# NIC_DP83848.net
KiCad netlist of a schematic drawn in Altium Designer
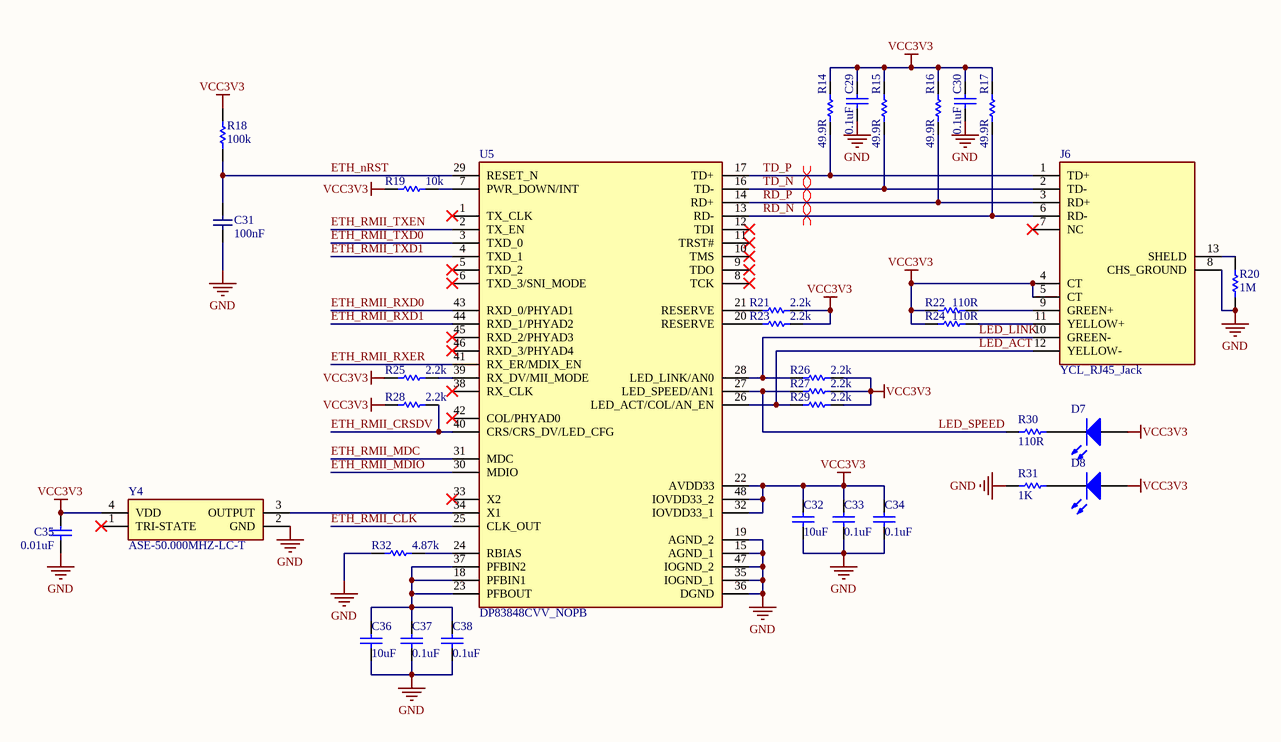
[diagram p0: NIC_DP83848.SchDoc]

(export (version "E")
  (design (tool "Eeschema 10.0.6"))
  (components
    (comp (ref "C29")
      (value "0.1uF")
      (footprint "SMD0603")
      (description "Capacitor (Semiconductor SIM Model)")
      (fields (field (name "PUBLISHER") "Altium Limited"))
      (libsource (lib "Miscellaneous Devices") (part "Cap Semi"))
    )
    (comp (ref "C30")
      (value "0.1uF")
      (footprint "SMD0603")
      (description "Capacitor (Semiconductor SIM Model)")
      (fields (field (name "PUBLISHER") "Altium Limited"))
      (libsource (lib "Miscellaneous Devices") (part "Cap Semi"))
    )
    (comp (ref "C31")
      (value "100nF")
      (footprint "SMD0603")
      (description "Capacitor (Semiconductor SIM Model)")
      (libsource (lib "SRV8") (part "Cap"))
    )
    (comp (ref "C32")
      (value "10uF")
      (footprint "SMD0603")
      (description "Capacitor (Semiconductor SIM Model)")
      (fields (field (name "PUBLISHER") "Altium Limited"))
      (libsource (lib "Miscellaneous Devices") (part "Cap Semi"))
    )
    (comp (ref "C33")
      (value "0.1uF")
      (footprint "SMD0603")
      (description "Capacitor (Semiconductor SIM Model)")
      (fields (field (name "PUBLISHER") "Altium Limited"))
      (libsource (lib "Miscellaneous Devices") (part "Cap Semi"))
    )
    (comp (ref "C34")
      (value "0.1uF")
      (footprint "SMD0603")
      (description "Capacitor (Semiconductor SIM Model)")
      (fields (field (name "PUBLISHER") "Altium Limited"))
      (libsource (lib "Miscellaneous Devices") (part "Cap Semi"))
    )
    (comp (ref "C35")
      (value "0.01uF")
      (footprint "SMD0603")
      (description "Capacitor (Semiconductor SIM Model)")
      (fields (field (name "Comment") "0.1uF") (field (name "PUBLISHER") "Altium Limited"))
      (libsource (lib "Miscellaneous Devices") (part "Cap Semi"))
    )
    (comp (ref "C36")
      (value "10uF")
      (footprint "SMD0603")
      (description "Capacitor (Semiconductor SIM Model)")
      (fields (field (name "PUBLISHER") "Altium Limited"))
      (libsource (lib "Miscellaneous Devices") (part "Cap Semi"))
    )
    (comp (ref "C37")
      (value "0.1uF")
      (footprint "SMD0603")
      (description "Capacitor (Semiconductor SIM Model)")
      (fields (field (name "PUBLISHER") "Altium Limited"))
      (libsource (lib "Miscellaneous Devices") (part "Cap Semi"))
    )
    (comp (ref "C38")
      (value "0.1uF")
      (footprint "SMD0603")
      (description "Capacitor (Semiconductor SIM Model)")
      (fields (field (name "PUBLISHER") "Altium Limited"))
      (libsource (lib "Miscellaneous Devices") (part "Cap Semi"))
    )
    (comp (ref "D7")
      (value "LED0")
      (footprint "SMD0603_LED")
      (description "Typical INFRARED GaAs LED")
      (fields (field (name "PUBLISHER") "Altium Limited"))
      (libsource (lib "Miscellaneous Devices") (part "LED0"))
    )
    (comp (ref "D8")
      (value "LED0")
      (footprint "SMD0603_LED")
      (description "Typical INFRARED GaAs LED")
      (fields (field (name "PUBLISHER") "Altium Limited"))
      (libsource (lib "Miscellaneous Devices") (part "LED0"))
    )
    (comp (ref "J6")
      (value "YCL_RJ45_Jack")
      (footprint "YCL_RJ45_Jack")
      (description "Connector")
      (fields (field (name "MANUFACTURER_PART_NUMBER") "J0011D21BNL"))
      (libsource (lib "ether_phy_lib") (part "YCL_RJ45_Jack"))
    )
    (comp (ref "R14")
      (value "49.9R")
      (footprint "SMD0603")
      (description "Semiconductor Resistor")
      (fields (field (name "PUBLISHER") "Altium Limited"))
      (libsource (lib "Miscellaneous Devices") (part "Res Semi"))
    )
    (comp (ref "R15")
      (value "49.9R")
      (footprint "SMD0603")
      (description "Semiconductor Resistor")
      (fields (field (name "PUBLISHER") "Altium Limited"))
      (libsource (lib "Miscellaneous Devices") (part "Res Semi"))
    )
    (comp (ref "R16")
      (value "49.9R")
      (footprint "SMD0603")
      (description "Semiconductor Resistor")
      (fields (field (name "PUBLISHER") "Altium Limited"))
      (libsource (lib "Miscellaneous Devices") (part "Res Semi"))
    )
    (comp (ref "R17")
      (value "49.9R")
      (footprint "SMD0603")
      (description "Semiconductor Resistor")
      (fields (field (name "PUBLISHER") "Altium Limited"))
      (libsource (lib "Miscellaneous Devices") (part "Res Semi"))
    )
    (comp (ref "R18")
      (value "100k")
      (footprint "SMD0603")
      (description "Semiconductor Resistor")
      (fields (field (name "Comment") "100K"))
      (libsource (lib "*") (part "Res"))
    )
    (comp (ref "R19")
      (value "10k")
      (footprint "SMD0603")
      (description "Semiconductor Resistor")
      (fields (field (name "PUBLISHER") "Altium Limited"))
      (libsource (lib "Miscellaneous Devices") (part "Res Semi"))
    )
    (comp (ref "R20")
      (value "1M")
      (footprint "SMD0603")
      (description "Semiconductor Resistor")
      (fields (field (name "PUBLISHER") "Altium Limited"))
      (libsource (lib "Miscellaneous Devices") (part "Res Semi"))
    )
    (comp (ref "R21")
      (value "2.2k")
      (footprint "SMD0603")
      (description "Semiconductor Resistor")
      (fields (field (name "PUBLISHER") "Altium Limited"))
      (libsource (lib "Miscellaneous Devices") (part "Res Semi"))
    )
    (comp (ref "R22")
      (value "110R")
      (footprint "SMD0603")
      (description "Semiconductor Resistor")
      (fields (field (name "PUBLISHER") "Altium Limited"))
      (libsource (lib "Miscellaneous Devices") (part "Res Semi"))
    )
    (comp (ref "R23")
      (value "2.2k")
      (footprint "SMD0603")
      (description "Semiconductor Resistor")
      (fields (field (name "PUBLISHER") "Altium Limited"))
      (libsource (lib "Miscellaneous Devices") (part "Res Semi"))
    )
    (comp (ref "R24")
      (value "110R")
      (footprint "SMD0603")
      (description "Semiconductor Resistor")
      (fields (field (name "PUBLISHER") "Altium Limited"))
      (libsource (lib "Miscellaneous Devices") (part "Res Semi"))
    )
    (comp (ref "R25")
      (value "2.2k")
      (footprint "SMD0603")
      (description "Semiconductor Resistor")
      (fields (field (name "PUBLISHER") "Altium Limited"))
      (libsource (lib "Miscellaneous Devices") (part "Res Semi"))
    )
    (comp (ref "R26")
      (value "2.2k")
      (footprint "SMD0603")
      (description "Semiconductor Resistor")
      (fields (field (name "PUBLISHER") "Altium Limited"))
      (libsource (lib "Miscellaneous Devices") (part "Res Semi"))
    )
    (comp (ref "R27")
      (value "2.2k")
      (footprint "SMD0603")
      (description "Semiconductor Resistor")
      (fields (field (name "PUBLISHER") "Altium Limited"))
      (libsource (lib "Miscellaneous Devices") (part "Res Semi"))
    )
    (comp (ref "R28")
      (value "2.2k")
      (footprint "SMD0603")
      (description "Semiconductor Resistor")
      (fields (field (name "PUBLISHER") "Altium Limited"))
      (libsource (lib "Miscellaneous Devices") (part "Res Semi"))
    )
    (comp (ref "R29")
      (value "2.2k")
      (footprint "SMD0603")
      (description "Semiconductor Resistor")
      (fields (field (name "PUBLISHER") "Altium Limited"))
      (libsource (lib "Miscellaneous Devices") (part "Res Semi"))
    )
    (comp (ref "R30")
      (value "110R")
      (footprint "SMD0603")
      (description "Semiconductor Resistor")
      (fields (field (name "Comment") "1K") (field (name "PUBLISHER") "Altium Limited"))
      (libsource (lib "Miscellaneous Devices") (part "Res Semi"))
    )
    (comp (ref "R31")
      (value "1K")
      (footprint "SMD0603")
      (description "Semiconductor Resistor")
      (fields (field (name "PUBLISHER") "Altium Limited"))
      (libsource (lib "Miscellaneous Devices") (part "Res Semi"))
    )
    (comp (ref "R32")
      (value "4.87k")
      (footprint "SMD0603")
      (description "Semiconductor Resistor")
      (fields (field (name "PUBLISHER") "Altium Limited"))
      (libsource (lib "Miscellaneous Devices") (part "Res Semi"))
    )
    (comp (ref "U5")
      (value "DP83848CVV_NOPB")
      (footprint "QFP50P900X900X160-48N")
      (description "Ethernet phy")
      (libsource (lib "ether_phy_lib") (part "DP83848CVV"))
    )
    (comp (ref "Y4")
      (value "ASE-50.000MHZ-LC-T")
      (footprint "OSC3225")
      (description "Crystal or Oscillator")
      (fields (field (name "MOUSER2 PART NUMBER") "815-ASE50.000MHZLCT"))
      (libsource (lib "ether_phy_lib") (part "ASE-50.000MHZ-LC-T"))
    )
  )
  (nets
    (net (code "1") (name "/ETH_RMII_CLK") (class "Default")
      (node (ref "U5") (pin "25") (pinfunction "CLK_OUT_25") (pintype "passive"))
    )
    (net (code "2") (name "/ETH_RMII_CRSDV") (class "Default")
      (node (ref "R28") (pin "1") (pinfunction "1_1") (pintype "passive"))
      (node (ref "U5") (pin "40") (pinfunction "CRS/CRS_DV/LED_CFG_40") (pintype "passive"))
    )
    (net (code "3") (name "/ETH_RMII_MDC") (class "Default")
      (node (ref "U5") (pin "31") (pinfunction "MDC_31") (pintype "passive"))
    )
    (net (code "4") (name "/ETH_RMII_MDIO") (class "Default")
      (node (ref "U5") (pin "30") (pinfunction "MDIO_30") (pintype "passive"))
    )
    (net (code "5") (name "/ETH_RMII_RXD0") (class "Default")
      (node (ref "U5") (pin "43") (pinfunction "RXD_0/PHYAD1_43") (pintype "passive"))
    )
    (net (code "6") (name "/ETH_RMII_RXD1") (class "Default")
      (node (ref "U5") (pin "44") (pinfunction "RXD_1/PHYAD2_44") (pintype "passive"))
    )
    (net (code "7") (name "/ETH_RMII_RXER") (class "Default")
      (node (ref "U5") (pin "41") (pinfunction "RX_ER/MDIX_EN_41") (pintype "passive"))
    )
    (net (code "8") (name "/ETH_RMII_TXD0") (class "Default")
      (node (ref "U5") (pin "3") (pinfunction "TXD_0_3") (pintype "passive"))
    )
    (net (code "9") (name "/ETH_RMII_TXD1") (class "Default")
      (node (ref "U5") (pin "4") (pinfunction "TXD_1_4") (pintype "passive"))
    )
    (net (code "10") (name "/ETH_RMII_TXEN") (class "Default")
      (node (ref "U5") (pin "2") (pinfunction "TX_EN_2") (pintype "passive"))
    )
    (net (code "11") (name "/ETH_nRST") (class "Default")
      (node (ref "C31") (pin "2") (pinfunction "2_2") (pintype "passive"))
      (node (ref "R18") (pin "1") (pinfunction "1_1") (pintype "passive"))
      (node (ref "U5") (pin "29") (pinfunction "RESET_N_29") (pintype "passive"))
    )
    (net (code "12") (name "/LED_ACT") (class "Default")
      (node (ref "J6") (pin "12") (pinfunction "YELLOW-_12") (pintype "passive"))
      (node (ref "R29") (pin "2") (pinfunction "2_2") (pintype "passive"))
      (node (ref "U5") (pin "26") (pinfunction "LED_ACT/COL/AN_EN_26") (pintype "passive"))
    )
    (net (code "13") (name "/LED_LINK") (class "Default")
      (node (ref "J6") (pin "10") (pinfunction "GREEN-_10") (pintype "passive"))
      (node (ref "R26") (pin "2") (pinfunction "2_2") (pintype "passive"))
      (node (ref "U5") (pin "28") (pinfunction "LED_LINK/AN0_28") (pintype "passive"))
    )
    (net (code "14") (name "/LED_SPEED") (class "Default")
      (node (ref "R27") (pin "1") (pinfunction "1_1") (pintype "passive"))
      (node (ref "R30") (pin "1") (pinfunction "1_1") (pintype "passive"))
      (node (ref "U5") (pin "27") (pinfunction "LED_SPEED/AN1_27") (pintype "passive"))
    )
    (net (code "15") (name "/RD_N") (class "Default")
      (node (ref "J6") (pin "6") (pinfunction "RD-_6") (pintype "passive"))
      (node (ref "R17") (pin "2") (pinfunction "2_2") (pintype "passive"))
      (node (ref "U5") (pin "13") (pinfunction "RD-_13") (pintype "passive"))
    )
    (net (code "16") (name "/RD_P") (class "Default")
      (node (ref "J6") (pin "3") (pinfunction "RD+_3") (pintype "passive"))
      (node (ref "R16") (pin "2") (pinfunction "2_2") (pintype "passive"))
      (node (ref "U5") (pin "14") (pinfunction "RD+_14") (pintype "passive"))
    )
    (net (code "17") (name "/TD_N") (class "Default")
      (node (ref "J6") (pin "2") (pinfunction "TD-_2") (pintype "passive"))
      (node (ref "R15") (pin "2") (pinfunction "2_2") (pintype "passive"))
      (node (ref "U5") (pin "16") (pinfunction "TD-_16") (pintype "passive"))
    )
    (net (code "18") (name "/TD_P") (class "Default")
      (node (ref "J6") (pin "1") (pinfunction "TD+_1") (pintype "passive"))
      (node (ref "R14") (pin "2") (pinfunction "2_2") (pintype "passive"))
      (node (ref "U5") (pin "17") (pinfunction "TD+_17") (pintype "passive"))
    )
    (net (code "19") (name "GND") (class "Default")
      (node (ref "C29") (pin "2") (pinfunction "2_2") (pintype "passive"))
      (node (ref "C30") (pin "2") (pinfunction "2_2") (pintype "passive"))
      (node (ref "C31") (pin "1") (pinfunction "1_1") (pintype "passive"))
      (node (ref "C32") (pin "2") (pinfunction "2_2") (pintype "passive"))
      (node (ref "C33") (pin "2") (pinfunction "2_2") (pintype "passive"))
      (node (ref "C34") (pin "2") (pinfunction "2_2") (pintype "passive"))
      (node (ref "C35") (pin "2") (pinfunction "2_2") (pintype "passive"))
      (node (ref "C36") (pin "2") (pinfunction "2_2") (pintype "passive"))
      (node (ref "C37") (pin "2") (pinfunction "2_2") (pintype "passive"))
      (node (ref "C38") (pin "2") (pinfunction "2_2") (pintype "passive"))
      (node (ref "J6") (pin "8") (pinfunction "CHS_GROUND_8") (pintype "passive"))
      (node (ref "R20") (pin "1") (pinfunction "1_1") (pintype "passive"))
      (node (ref "R31") (pin "1") (pinfunction "1_1") (pintype "passive"))
      (node (ref "R32") (pin "2") (pinfunction "2_2") (pintype "passive"))
      (node (ref "U5") (pin "15") (pinfunction "AGND_1_15") (pintype "passive"))
      (node (ref "U5") (pin "19") (pinfunction "AGND_2_19") (pintype "passive"))
      (node (ref "U5") (pin "35") (pinfunction "IOGND_1_35") (pintype "passive"))
      (node (ref "U5") (pin "36") (pinfunction "DGND_36") (pintype "passive"))
      (node (ref "U5") (pin "47") (pinfunction "IOGND_2_47") (pintype "passive"))
      (node (ref "Y4") (pin "2") (pinfunction "GND_2") (pintype "passive"))
    )
    (net (code "20") (name "Net-(D7-K)") (class "Default")
      (node (ref "D7") (pin "2") (pinfunction "K_2") (pintype "passive"))
      (node (ref "R30") (pin "2") (pinfunction "2_2") (pintype "passive"))
    )
    (net (code "21") (name "Net-(D8-K)") (class "Default")
      (node (ref "D8") (pin "2") (pinfunction "K_2") (pintype "passive"))
      (node (ref "R31") (pin "2") (pinfunction "2_2") (pintype "passive"))
    )
    (net (code "22") (name "Net-(J6-GREEN+)") (class "Default")
      (node (ref "J6") (pin "9") (pinfunction "GREEN+_9") (pintype "passive"))
      (node (ref "R22") (pin "2") (pinfunction "2_2") (pintype "passive"))
    )
    (net (code "23") (name "Net-(J6-SHELD)") (class "Default")
      (node (ref "J6") (pin "13") (pinfunction "SHELD_13") (pintype "passive"))
      (node (ref "R20") (pin "2") (pinfunction "2_2") (pintype "passive"))
    )
    (net (code "24") (name "Net-(J6-YELLOW+)") (class "Default")
      (node (ref "J6") (pin "11") (pinfunction "YELLOW+_11") (pintype "passive"))
      (node (ref "R24") (pin "2") (pinfunction "2_2") (pintype "passive"))
    )
    (net (code "25") (name "Net-(R21-Pad2)") (class "Default")
      (node (ref "R21") (pin "2") (pinfunction "2_2") (pintype "passive"))
      (node (ref "U5") (pin "21") (pinfunction "RESERVE_21") (pintype "passive"))
    )
    (net (code "26") (name "Net-(R23-Pad1)") (class "Default")
      (node (ref "R23") (pin "1") (pinfunction "1_1") (pintype "passive"))
      (node (ref "U5") (pin "20") (pinfunction "RESERVE_20") (pintype "passive"))
    )
    (net (code "27") (name "Net-(U5-PFBIN1)") (class "Default")
      (node (ref "C36") (pin "1") (pinfunction "1_1") (pintype "passive"))
      (node (ref "C37") (pin "1") (pinfunction "1_1") (pintype "passive"))
      (node (ref "C38") (pin "1") (pinfunction "1_1") (pintype "passive"))
      (node (ref "U5") (pin "18") (pinfunction "PFBIN1_18") (pintype "passive"))
      (node (ref "U5") (pin "23") (pinfunction "PFBOUT_23") (pintype "passive"))
      (node (ref "U5") (pin "37") (pinfunction "PFBIN2_37") (pintype "passive"))
    )
    (net (code "28") (name "Net-(U5-PWR_DOWN{slash}INT)") (class "Default")
      (node (ref "R19") (pin "1") (pinfunction "1_1") (pintype "passive"))
      (node (ref "U5") (pin "7") (pinfunction "PWR_DOWN/INT_7") (pintype "passive"))
    )
    (net (code "29") (name "Net-(U5-RBIAS)") (class "Default")
      (node (ref "R32") (pin "1") (pinfunction "1_1") (pintype "passive"))
      (node (ref "U5") (pin "24") (pinfunction "RBIAS_24") (pintype "passive"))
    )
    (net (code "30") (name "Net-(U5-RX_DV{slash}MII_MODE)") (class "Default")
      (node (ref "R25") (pin "1") (pinfunction "1_1") (pintype "passive"))
      (node (ref "U5") (pin "39") (pinfunction "RX_DV/MII_MODE_39") (pintype "passive"))
    )
    (net (code "31") (name "Net-(U5-X1)") (class "Default")
      (node (ref "U5") (pin "34") (pinfunction "X1_34") (pintype "passive"))
      (node (ref "Y4") (pin "3") (pinfunction "OUTPUT_3") (pintype "passive"))
    )
    (net (code "32") (name "VCC3V3") (class "Default")
      (node (ref "C29") (pin "1") (pinfunction "1_1") (pintype "passive"))
      (node (ref "C30") (pin "1") (pinfunction "1_1") (pintype "passive"))
      (node (ref "C32") (pin "1") (pinfunction "1_1") (pintype "passive"))
      (node (ref "C33") (pin "1") (pinfunction "1_1") (pintype "passive"))
      (node (ref "C34") (pin "1") (pinfunction "1_1") (pintype "passive"))
      (node (ref "C35") (pin "1") (pinfunction "1_1") (pintype "passive"))
      (node (ref "D7") (pin "1") (pinfunction "A_1") (pintype "passive"))
      (node (ref "D8") (pin "1") (pinfunction "A_1") (pintype "passive"))
      (node (ref "J6") (pin "4") (pinfunction "CT_4") (pintype "passive"))
      (node (ref "J6") (pin "5") (pinfunction "CT_5") (pintype "passive"))
      (node (ref "R14") (pin "1") (pinfunction "1_1") (pintype "passive"))
      (node (ref "R15") (pin "1") (pinfunction "1_1") (pintype "passive"))
      (node (ref "R16") (pin "1") (pinfunction "1_1") (pintype "passive"))
      (node (ref "R17") (pin "1") (pinfunction "1_1") (pintype "passive"))
      (node (ref "R18") (pin "2") (pinfunction "2_2") (pintype "passive"))
      (node (ref "R19") (pin "2") (pinfunction "2_2") (pintype "passive"))
      (node (ref "R21") (pin "1") (pinfunction "1_1") (pintype "passive"))
      (node (ref "R22") (pin "1") (pinfunction "1_1") (pintype "passive"))
      (node (ref "R23") (pin "2") (pinfunction "2_2") (pintype "passive"))
      (node (ref "R24") (pin "1") (pinfunction "1_1") (pintype "passive"))
      (node (ref "R25") (pin "2") (pinfunction "2_2") (pintype "passive"))
      (node (ref "R26") (pin "1") (pinfunction "1_1") (pintype "passive"))
      (node (ref "R27") (pin "2") (pinfunction "2_2") (pintype "passive"))
      (node (ref "R28") (pin "2") (pinfunction "2_2") (pintype "passive"))
      (node (ref "R29") (pin "1") (pinfunction "1_1") (pintype "passive"))
      (node (ref "U5") (pin "22") (pinfunction "AVDD33_22") (pintype "passive"))
      (node (ref "U5") (pin "32") (pinfunction "IOVDD33_1_32") (pintype "passive"))
      (node (ref "U5") (pin "48") (pinfunction "IOVDD33_2_48") (pintype "passive"))
      (node (ref "Y4") (pin "4") (pinfunction "VDD_4") (pintype "passive"))
    )
    (net (code "33") (name "unconnected-(J6-NC-Pad7)") (class "Default")
      (node (ref "J6") (pin "7") (pinfunction "NC_7") (pintype "passive+no_connect"))
    )
    (net (code "34") (name "unconnected-(U5-COL{slash}PHYAD0-Pad42)") (class "Default")
      (node (ref "U5") (pin "42") (pinfunction "COL/PHYAD0_42") (pintype "passive+no_connect"))
    )
    (net (code "35") (name "unconnected-(U5-RXD_2{slash}PHYAD3-Pad45)") (class "Default")
      (node (ref "U5") (pin "45") (pinfunction "RXD_2/PHYAD3_45") (pintype "passive+no_connect"))
    )
    (net (code "36") (name "unconnected-(U5-RXD_3{slash}PHYAD4-Pad46)") (class "Default")
      (node (ref "U5") (pin "46") (pinfunction "RXD_3/PHYAD4_46") (pintype "passive+no_connect"))
    )
    (net (code "37") (name "unconnected-(U5-RX_CLK-Pad38)") (class "Default")
      (node (ref "U5") (pin "38") (pinfunction "RX_CLK_38") (pintype "passive+no_connect"))
    )
    (net (code "38") (name "unconnected-(U5-TCK-Pad8)") (class "Default")
      (node (ref "U5") (pin "8") (pinfunction "TCK_8") (pintype "passive+no_connect"))
    )
    (net (code "39") (name "unconnected-(U5-TDI-Pad12)") (class "Default")
      (node (ref "U5") (pin "12") (pinfunction "TDI_12") (pintype "passive+no_connect"))
    )
    (net (code "40") (name "unconnected-(U5-TDO-Pad9)") (class "Default")
      (node (ref "U5") (pin "9") (pinfunction "TDO_9") (pintype "passive+no_connect"))
    )
    (net (code "41") (name "unconnected-(U5-TMS-Pad10)") (class "Default")
      (node (ref "U5") (pin "10") (pinfunction "TMS_10") (pintype "passive+no_connect"))
    )
    (net (code "42") (name "unconnected-(U5-TRST#-Pad11)") (class "Default")
      (node (ref "U5") (pin "11") (pinfunction "TRST#_11") (pintype "passive+no_connect"))
    )
    (net (code "43") (name "unconnected-(U5-TXD_2-Pad5)") (class "Default")
      (node (ref "U5") (pin "5") (pinfunction "TXD_2_5") (pintype "passive+no_connect"))
    )
    (net (code "44") (name "unconnected-(U5-TXD_3{slash}SNI_MODE-Pad6)") (class "Default")
      (node (ref "U5") (pin "6") (pinfunction "TXD_3/SNI_MODE_6") (pintype "passive+no_connect"))
    )
    (net (code "45") (name "unconnected-(U5-TX_CLK-Pad1)") (class "Default")
      (node (ref "U5") (pin "1") (pinfunction "TX_CLK_1") (pintype "passive+no_connect"))
    )
    (net (code "46") (name "unconnected-(U5-X2-Pad33)") (class "Default")
      (node (ref "U5") (pin "33") (pinfunction "X2_33") (pintype "passive+no_connect"))
    )
    (net (code "47") (name "unconnected-(Y4-TRI-STATE-Pad1)") (class "Default")
      (node (ref "Y4") (pin "1") (pinfunction "TRI-STATE_1") (pintype "passive+no_connect"))
    )
  )
)
